# audio_jack_passthru_bantam.net
KiCad netlist of a schematic drawn in EAGLE
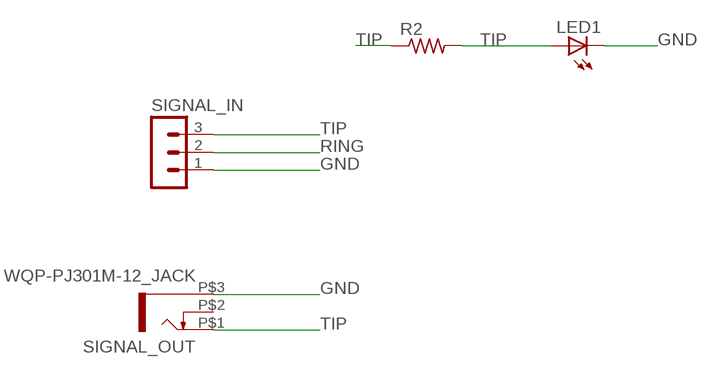
[diagram p0: schematic, sheet 1]

(export (version "E")
  (design (tool "Eeschema 10.0.6"))
  (components
    (comp (ref "LED1")
      (value "LED3MM")
      (footprint "eagle-import:LED3MM")
      (libsource (lib "eagle-import") (part "LED3MM"))
    )
    (comp (ref "R2")
      (value "R-US_0207/9")
      (footprint "eagle-import:0207_9")
      (libsource (lib "eagle-import") (part "R-US_0207/9"))
    )
    (comp (ref "SIGNAL_IN")
      (value "MA03-1")
      (footprint "eagle-import:MA03-1")
      (libsource (lib "eagle-import") (part "MA03-1"))
    )
    (comp (ref "SIGNAL_OUT")
      (value "WQP-PJ301M-12_JACK")
      (footprint "eagle-import:WQP-PJ301M-12_JACK")
      (libsource (lib "eagle-import") (part "WQP-PJ301M-12_JACK"))
    )
  )
  (nets
    (net (code "1") (name "/GND") (class "Default")
      (node (ref "LED1") (pin "K") (pinfunction "C_K") (pintype "passive"))
      (node (ref "SIGNAL_IN") (pin "1") (pinfunction "1_1") (pintype "passive"))
      (node (ref "SIGNAL_OUT") (pin "P$3") (pinfunction "1_P$3") (pintype "passive"))
    )
    (net (code "2") (name "/RING") (class "Default")
      (node (ref "SIGNAL_IN") (pin "2") (pinfunction "2_2") (pintype "passive"))
    )
    (net (code "3") (name "/TIP") (class "Default")
      (node (ref "LED1") (pin "A") (pinfunction "A_A") (pintype "passive"))
      (node (ref "R2") (pin "1") (pinfunction "1_1") (pintype "passive"))
      (node (ref "R2") (pin "2") (pinfunction "2_2") (pintype "passive"))
      (node (ref "SIGNAL_IN") (pin "3") (pinfunction "3_3") (pintype "passive"))
      (node (ref "SIGNAL_OUT") (pin "P$1") (pinfunction "2_P$1") (pintype "passive"))
    )
    (net (code "4") (name "unconnected-(SIGNAL_OUT-3-PadP$2)") (class "Default")
      (node (ref "SIGNAL_OUT") (pin "P$2") (pinfunction "3_P$2") (pintype "passive"))
    )
  )
)
